# LeakMonitorMonitor.net
KiCad netlist of a schematic drawn in EAGLE
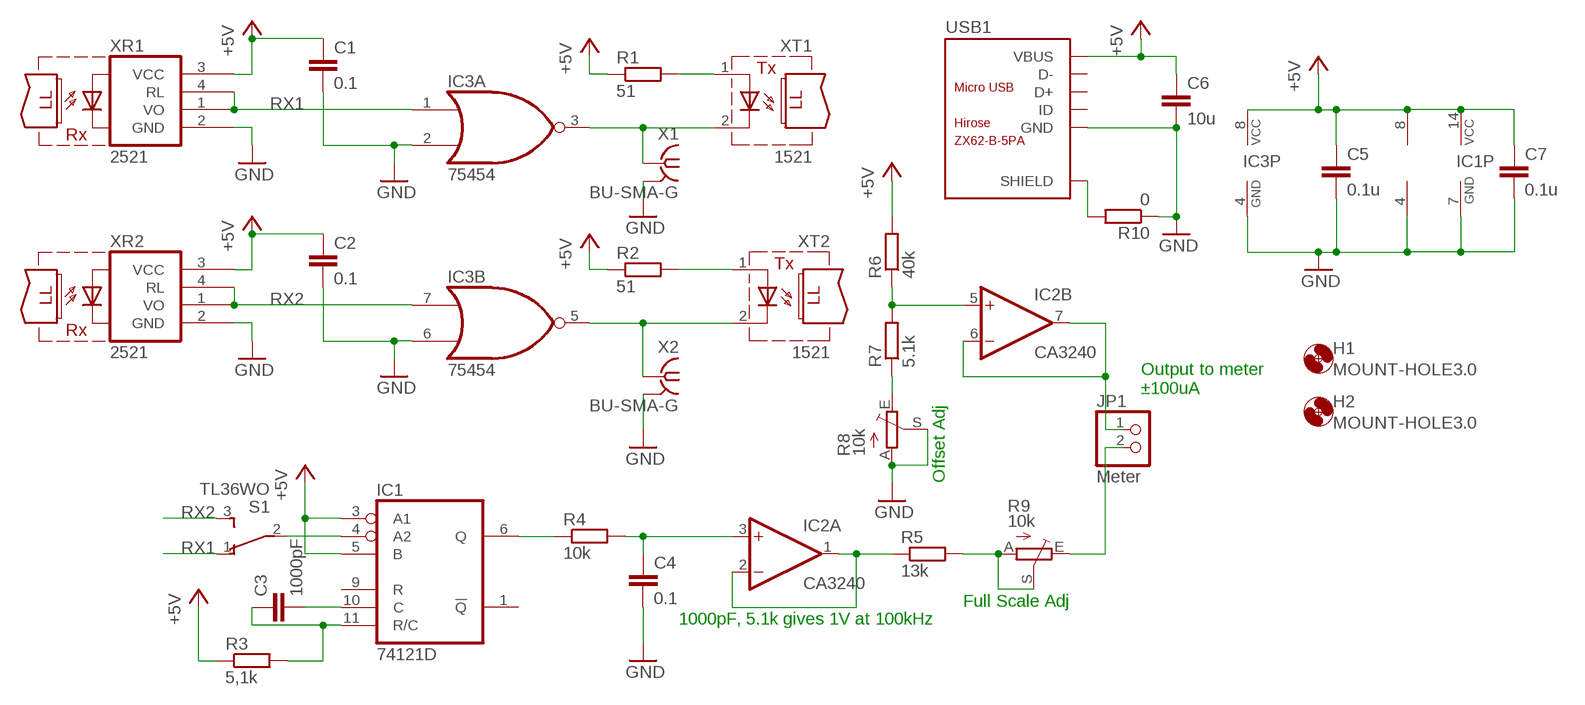
[diagram p0: schematic, sheet 1]

(export (version "E")
  (design (tool "Eeschema 10.0.6"))
  (components
    (comp (ref "C1")
      (value "0.1")
      (footprint "eagle-import:C0805")
      (libsource (lib "eagle-import") (part "C-EUC0805"))
    )
    (comp (ref "C2")
      (value "0.1")
      (footprint "eagle-import:C0805")
      (libsource (lib "eagle-import") (part "C-EUC0805"))
    )
    (comp (ref "C3")
      (value "1000pF")
      (footprint "eagle-import:C0805")
      (libsource (lib "eagle-import") (part "C-EUC0805"))
    )
    (comp (ref "C4")
      (value "0.1")
      (footprint "eagle-import:C0805")
      (libsource (lib "eagle-import") (part "C-EUC0805"))
    )
    (comp (ref "C5")
      (value "0.1u")
      (footprint "eagle-import:C0805")
      (libsource (lib "eagle-import") (part "C-EUC0805"))
    )
    (comp (ref "C6")
      (value "10u")
      (footprint "eagle-import:C1206")
      (libsource (lib "eagle-import") (part "C-EUC1206"))
    )
    (comp (ref "C7")
      (value "0.1u")
      (footprint "eagle-import:C0805")
      (libsource (lib "eagle-import") (part "C-EUC0805"))
    )
    (comp (ref "H1")
      (value "MOUNT-HOLE3.0")
      (footprint "eagle-import:3,0")
      (libsource (lib "eagle-import") (part "MOUNT-HOLE3.0"))
    )
    (comp (ref "H2")
      (value "MOUNT-HOLE3.0")
      (footprint "eagle-import:3,0")
      (libsource (lib "eagle-import") (part "MOUNT-HOLE3.0"))
    )
    (comp (ref "IC1")
      (value "74121D")
      (footprint "eagle-import:SO14")
      (libsource (lib "eagle-import") (part "74121D"))
    )
    (comp (ref "IC2")
      (value "CA3240")
      (footprint "eagle-import:SO08")
      (libsource (lib "eagle-import") (part "CA3240ED"))
    )
    (comp (ref "IC3")
      (value "75454")
      (footprint "eagle-import:D_R-PDSO-G8")
      (libsource (lib "eagle-import") (part "SN75454BD"))
    )
    (comp (ref "JP1")
      (value "Meter")
      (footprint "eagle-import:1X02")
      (libsource (lib "eagle-import") (part "PINHD-1X2"))
    )
    (comp (ref "R1")
      (value "51")
      (footprint "eagle-import:M0805")
      (libsource (lib "eagle-import") (part "R-EU_M0805"))
    )
    (comp (ref "R2")
      (value "51")
      (footprint "eagle-import:M0805")
      (libsource (lib "eagle-import") (part "R-EU_M0805"))
    )
    (comp (ref "R3")
      (value "5,1k")
      (footprint "eagle-import:M0805")
      (libsource (lib "eagle-import") (part "R-EU_M0805"))
    )
    (comp (ref "R4")
      (value "10k")
      (footprint "eagle-import:M0805")
      (libsource (lib "eagle-import") (part "R-EU_M0805"))
    )
    (comp (ref "R5")
      (value "13k")
      (footprint "eagle-import:M0805")
      (libsource (lib "eagle-import") (part "R-EU_M0805"))
    )
    (comp (ref "R6")
      (value "40k")
      (footprint "eagle-import:M0805")
      (libsource (lib "eagle-import") (part "R-EU_M0805"))
    )
    (comp (ref "R7")
      (value "5.1k")
      (footprint "eagle-import:M0805")
      (libsource (lib "eagle-import") (part "R-EU_M0805"))
    )
    (comp (ref "R8")
      (value "10k")
      (footprint "eagle-import:B25X")
      (libsource (lib "eagle-import") (part "TRIM_EU-B25X"))
    )
    (comp (ref "R9")
      (value "10k")
      (footprint "eagle-import:B25X")
      (libsource (lib "eagle-import") (part "TRIM_EU-B25X"))
    )
    (comp (ref "R10")
      (value "0")
      (footprint "eagle-import:R0805")
      (libsource (lib "eagle-import") (part "R-EU_R0805"))
    )
    (comp (ref "S1")
      (value "TL36WO")
      (footprint "eagle-import:TL3XWO")
      (libsource (lib "eagle-import") (part "TL36WO"))
    )
    (comp (ref "USB1")
      (value "ZX62-B-5PA")
      (footprint "eagle-import:MICRO-USB5+6P-SMD-0.65-AB")
      (libsource (lib "eagle-import") (part "MICRO-USB-SMD(ZX62-B-5PA)"))
    )
    (comp (ref "X1")
      (value "BU-SMA-G")
      (footprint "eagle-import:BU-SMA-G")
      (libsource (lib "eagle-import") (part "BU-SMA-G"))
    )
    (comp (ref "X2")
      (value "BU-SMA-G")
      (footprint "eagle-import:BU-SMA-G")
      (libsource (lib "eagle-import") (part "BU-SMA-G"))
    )
    (comp (ref "XR1")
      (value "2521")
      (footprint "eagle-import:HFBR-15X3")
      (fields (field (name "MF") "AGILENT TECHNOLOGIES") (field (name "MPN") "HFBR-2521"))
      (libsource (lib "eagle-import") (part "HFBR-2521"))
    )
    (comp (ref "XR2")
      (value "2521")
      (footprint "eagle-import:HFBR-15X3")
      (fields (field (name "MF") "AGILENT TECHNOLOGIES") (field (name "MPN") "HFBR-2521"))
      (libsource (lib "eagle-import") (part "HFBR-2521"))
    )
    (comp (ref "XT1")
      (value "1521")
      (footprint "eagle-import:HFBR-15X3")
      (fields (field (name "MF") "AGILENT TECHNOLOGIES") (field (name "MPN") "HFBR-1521"))
      (libsource (lib "eagle-import") (part "HFBR-1521"))
    )
    (comp (ref "XT2")
      (value "1521")
      (footprint "eagle-import:HFBR-15X3")
      (fields (field (name "MF") "AGILENT TECHNOLOGIES") (field (name "MPN") "HFBR-1521"))
      (libsource (lib "eagle-import") (part "HFBR-1521"))
    )
  )
  (nets
    (net (code "1") (name "+5V") (class "Default")
      (node (ref "C1") (pin "1") (pinfunction "1_1") (pintype "passive"))
      (node (ref "C2") (pin "1") (pinfunction "1_1") (pintype "passive"))
      (node (ref "C5") (pin "1") (pinfunction "1_1") (pintype "passive"))
      (node (ref "C6") (pin "1") (pinfunction "1_1") (pintype "passive"))
      (node (ref "C7") (pin "1") (pinfunction "1_1") (pintype "passive"))
      (node (ref "IC1") (pin "14") (pinfunction "VCC_14") (pintype "power_in"))
      (node (ref "IC1") (pin "3") (pinfunction "A1_3") (pintype "input"))
      (node (ref "IC1") (pin "5") (pinfunction "B_5") (pintype "input"))
      (node (ref "IC2") (pin "8") (pinfunction "V+_8") (pintype "power_in"))
      (node (ref "IC3") (pin "8") (pinfunction "VCC_8") (pintype "power_in"))
      (node (ref "R1") (pin "1") (pinfunction "1_1") (pintype "passive"))
      (node (ref "R2") (pin "1") (pinfunction "1_1") (pintype "passive"))
      (node (ref "R3") (pin "1") (pinfunction "1_1") (pintype "passive"))
      (node (ref "R6") (pin "2") (pinfunction "2_2") (pintype "passive"))
      (node (ref "USB1") (pin "1") (pinfunction "VBUS_1") (pintype "power_in"))
      (node (ref "XR1") (pin "3") (pinfunction "VCC_3") (pintype "power_in"))
      (node (ref "XR2") (pin "3") (pinfunction "VCC_3") (pintype "power_in"))
    )
    (net (code "2") (name "/RX1") (class "Default")
      (node (ref "IC3") (pin "1") (pinfunction "I0_1") (pintype "input"))
      (node (ref "S1") (pin "1") (pinfunction "O_1") (pintype "passive"))
      (node (ref "XR1") (pin "1") (pinfunction "VO_1") (pintype "passive"))
      (node (ref "XR1") (pin "4") (pinfunction "RL_4") (pintype "passive"))
    )
    (net (code "3") (name "/RX2") (class "Default")
      (node (ref "IC3") (pin "7") (pinfunction "I0_7") (pintype "input"))
      (node (ref "S1") (pin "3") (pinfunction "S_3") (pintype "passive"))
      (node (ref "XR2") (pin "1") (pinfunction "VO_1") (pintype "passive"))
      (node (ref "XR2") (pin "4") (pinfunction "RL_4") (pintype "passive"))
    )
    (net (code "4") (name "GND") (class "Default")
      (node (ref "C1") (pin "2") (pinfunction "2_2") (pintype "passive"))
      (node (ref "C2") (pin "2") (pinfunction "2_2") (pintype "passive"))
      (node (ref "C4") (pin "2") (pinfunction "2_2") (pintype "passive"))
      (node (ref "C5") (pin "2") (pinfunction "2_2") (pintype "passive"))
      (node (ref "C6") (pin "2") (pinfunction "2_2") (pintype "passive"))
      (node (ref "C7") (pin "2") (pinfunction "2_2") (pintype "passive"))
      (node (ref "IC1") (pin "7") (pinfunction "GND_7") (pintype "power_in"))
      (node (ref "IC2") (pin "4") (pinfunction "V-_4") (pintype "power_in"))
      (node (ref "IC3") (pin "2") (pinfunction "I1_2") (pintype "input"))
      (node (ref "IC3") (pin "4") (pinfunction "GND_4") (pintype "power_in"))
      (node (ref "IC3") (pin "6") (pinfunction "I1_6") (pintype "input"))
      (node (ref "R10") (pin "1") (pinfunction "1_1") (pintype "passive"))
      (node (ref "R8") (pin "A") (pinfunction "A_A") (pintype "passive"))
      (node (ref "R8") (pin "S") (pinfunction "S_S") (pintype "passive"))
      (node (ref "USB1") (pin "5") (pinfunction "GND_5") (pintype "power_in"))
      (node (ref "X1") (pin "2") (pinfunction "2_2") (pintype "passive"))
      (node (ref "X1") (pin "3") (pinfunction "2_3") (pintype "passive"))
      (node (ref "X1") (pin "4") (pinfunction "2_4") (pintype "passive"))
      (node (ref "X1") (pin "5") (pinfunction "2_5") (pintype "passive"))
      (node (ref "X2") (pin "2") (pinfunction "2_2") (pintype "passive"))
      (node (ref "X2") (pin "3") (pinfunction "2_3") (pintype "passive"))
      (node (ref "X2") (pin "4") (pinfunction "2_4") (pintype "passive"))
      (node (ref "X2") (pin "5") (pinfunction "2_5") (pintype "passive"))
      (node (ref "XR1") (pin "2") (pinfunction "GND_2") (pintype "power_in"))
      (node (ref "XR2") (pin "2") (pinfunction "GND_2") (pintype "power_in"))
    )
    (net (code "5") (name "Net-(IC1A-A2)") (class "Default")
      (node (ref "IC1") (pin "4") (pinfunction "A2_4") (pintype "input"))
      (node (ref "S1") (pin "2") (pinfunction "P_2") (pintype "passive"))
    )
    (net (code "6") (name "Net-(IC1A-C)") (class "Default")
      (node (ref "C3") (pin "2") (pinfunction "2_2") (pintype "passive"))
      (node (ref "IC1") (pin "10") (pinfunction "C_10") (pintype "input"))
    )
    (net (code "7") (name "Net-(IC1A-Q)") (class "Default")
      (node (ref "IC1") (pin "6") (pinfunction "Q_6") (pintype "output"))
      (node (ref "R4") (pin "1") (pinfunction "1_1") (pintype "passive"))
    )
    (net (code "8") (name "Net-(IC1A-R{slash}C)") (class "Default")
      (node (ref "C3") (pin "1") (pinfunction "1_1") (pintype "passive"))
      (node (ref "IC1") (pin "11") (pinfunction "R/C_11") (pintype "input"))
      (node (ref "R3") (pin "2") (pinfunction "2_2") (pintype "passive"))
    )
    (net (code "9") (name "Net-(IC2A-+IN)") (class "Default")
      (node (ref "C4") (pin "1") (pinfunction "1_1") (pintype "passive"))
      (node (ref "IC2") (pin "3") (pinfunction "+IN_3") (pintype "input"))
      (node (ref "R4") (pin "2") (pinfunction "2_2") (pintype "passive"))
    )
    (net (code "10") (name "Net-(IC2A--IN)") (class "Default")
      (node (ref "IC2") (pin "1") (pinfunction "OUT_1") (pintype "output"))
      (node (ref "IC2") (pin "2") (pinfunction "-IN_2") (pintype "input"))
      (node (ref "R5") (pin "1") (pinfunction "1_1") (pintype "passive"))
    )
    (net (code "11") (name "Net-(IC2B-+IN)") (class "Default")
      (node (ref "IC2") (pin "5") (pinfunction "+IN_5") (pintype "input"))
      (node (ref "R6") (pin "1") (pinfunction "1_1") (pintype "passive"))
      (node (ref "R7") (pin "2") (pinfunction "2_2") (pintype "passive"))
    )
    (net (code "12") (name "Net-(IC2B--IN)") (class "Default")
      (node (ref "IC2") (pin "6") (pinfunction "-IN_6") (pintype "input"))
      (node (ref "IC2") (pin "7") (pinfunction "OUT_7") (pintype "output"))
      (node (ref "JP1") (pin "1") (pinfunction "1_1") (pintype "passive"))
    )
    (net (code "13") (name "Net-(IC3A-O)") (class "Default")
      (node (ref "IC3") (pin "3") (pinfunction "O_3") (pintype "output"))
      (node (ref "X1") (pin "1") (pinfunction "1_1") (pintype "passive"))
      (node (ref "XT1") (pin "2") (pinfunction "C_2") (pintype "passive"))
    )
    (net (code "14") (name "Net-(IC3B-O)") (class "Default")
      (node (ref "IC3") (pin "5") (pinfunction "O_5") (pintype "output"))
      (node (ref "X2") (pin "1") (pinfunction "1_1") (pintype "passive"))
      (node (ref "XT2") (pin "2") (pinfunction "C_2") (pintype "passive"))
    )
    (net (code "15") (name "Net-(JP1-Pad2)") (class "Default")
      (node (ref "JP1") (pin "2") (pinfunction "2_2") (pintype "passive"))
      (node (ref "R9") (pin "E") (pinfunction "E_E") (pintype "passive"))
    )
    (net (code "16") (name "Net-(R5-Pad2)") (class "Default")
      (node (ref "R5") (pin "2") (pinfunction "2_2") (pintype "passive"))
      (node (ref "R9") (pin "A") (pinfunction "A_A") (pintype "passive"))
      (node (ref "R9") (pin "S") (pinfunction "S_S") (pintype "passive"))
    )
    (net (code "17") (name "Net-(R7-Pad1)") (class "Default")
      (node (ref "R7") (pin "1") (pinfunction "1_1") (pintype "passive"))
      (node (ref "R8") (pin "E") (pinfunction "E_E") (pintype "passive"))
    )
    (net (code "18") (name "Net-(R10-Pad2)") (class "Default")
      (node (ref "R10") (pin "2") (pinfunction "2_2") (pintype "passive"))
      (node (ref "USB1") (pin "P1") (pinfunction "SHIELD_P1") (pintype "power_in"))
      (node (ref "USB1") (pin "P2") (pinfunction "SHIELD_P2") (pintype "power_in"))
      (node (ref "USB1") (pin "P3") (pinfunction "SHIELD_P3") (pintype "power_in"))
      (node (ref "USB1") (pin "P4") (pinfunction "SHIELD_P4") (pintype "power_in"))
      (node (ref "USB1") (pin "P5") (pinfunction "SHIELD_P5") (pintype "power_in"))
      (node (ref "USB1") (pin "P6") (pinfunction "SHIELD_P6") (pintype "power_in"))
    )
    (net (code "19") (name "Net-(XT1-A)") (class "Default")
      (node (ref "R1") (pin "2") (pinfunction "2_2") (pintype "passive"))
      (node (ref "XT1") (pin "1") (pinfunction "A_1") (pintype "passive"))
    )
    (net (code "20") (name "Net-(XT2-A)") (class "Default")
      (node (ref "R2") (pin "2") (pinfunction "2_2") (pintype "passive"))
      (node (ref "XT2") (pin "1") (pinfunction "A_1") (pintype "passive"))
    )
    (net (code "21") (name "unconnected-(IC1A-R-Pad9)") (class "Default")
      (node (ref "IC1") (pin "9") (pinfunction "R_9") (pintype "input"))
    )
    (net (code "22") (name "unconnected-(IC1A-~{Q}-Pad1)") (class "Default")
      (node (ref "IC1") (pin "1") (pinfunction "~{Q}_1") (pintype "output"))
    )
    (net (code "23") (name "unconnected-(USB1-D+-Pad3)") (class "Default")
      (node (ref "USB1") (pin "3") (pinfunction "D+_3") (pintype "bidirectional"))
    )
    (net (code "24") (name "unconnected-(USB1-D--Pad2)") (class "Default")
      (node (ref "USB1") (pin "2") (pinfunction "D-_2") (pintype "bidirectional"))
    )
    (net (code "25") (name "unconnected-(USB1-ID-Pad4)") (class "Default")
      (node (ref "USB1") (pin "4") (pinfunction "ID_4") (pintype "bidirectional"))
    )
  )
)
